# SH-SwitchNode-CT1_Shield.net
KiCad netlist of a schematic drawn in EAGLE
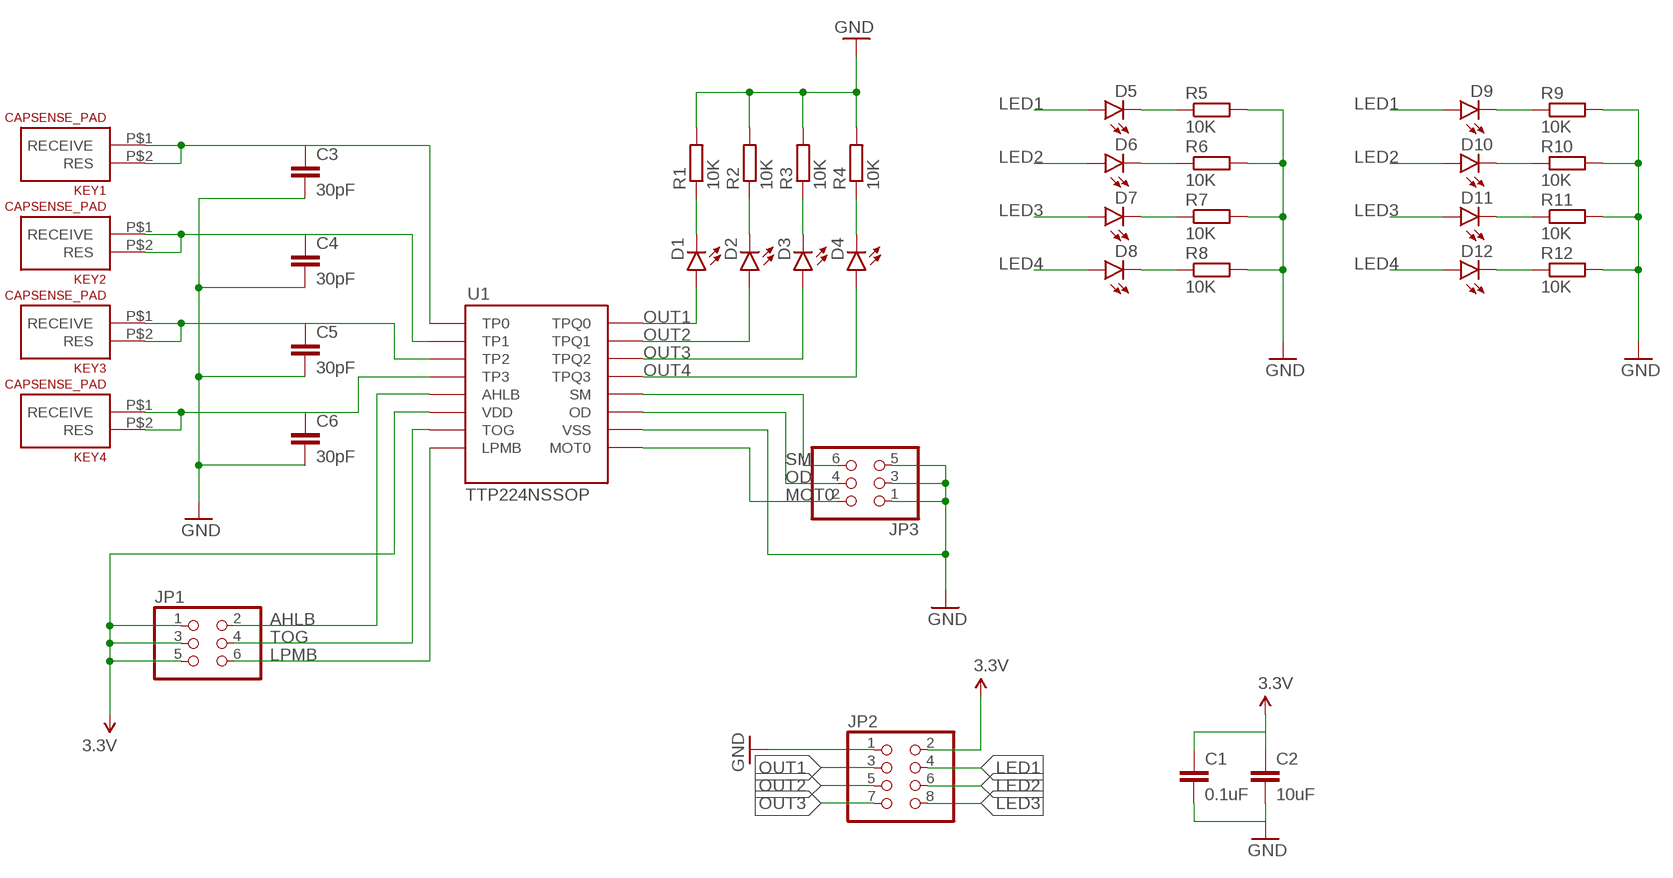
[diagram p0: schematic, sheet 1]

(export (version "E")
  (design (tool "Eeschema 10.0.6"))
  (components
    (comp (ref "C1")
      (value "0.1uF")
      (footprint "eagle-import:0805")
      (libsource (lib "eagle-import") (part "CAP0805"))
    )
    (comp (ref "C2")
      (value "10uF")
      (footprint "eagle-import:0805")
      (libsource (lib "eagle-import") (part "CAP0805"))
    )
    (comp (ref "C3")
      (value "30pF")
      (footprint "eagle-import:0805")
      (libsource (lib "eagle-import") (part "CAP0805"))
    )
    (comp (ref "C4")
      (value "30pF")
      (footprint "eagle-import:0805")
      (libsource (lib "eagle-import") (part "CAP0805"))
    )
    (comp (ref "C5")
      (value "30pF")
      (footprint "eagle-import:0805")
      (libsource (lib "eagle-import") (part "CAP0805"))
    )
    (comp (ref "C6")
      (value "30pF")
      (footprint "eagle-import:0805")
      (libsource (lib "eagle-import") (part "CAP0805"))
    )
    (comp (ref "D1")
      (value "LED1206-BOTTOM")
      (footprint "eagle-import:LED-1206-BOTTOM")
      (libsource (lib "eagle-import") (part "LED1206-BOTTOM"))
    )
    (comp (ref "D2")
      (value "LED1206-BOTTOM")
      (footprint "eagle-import:LED-1206-BOTTOM")
      (libsource (lib "eagle-import") (part "LED1206-BOTTOM"))
    )
    (comp (ref "D3")
      (value "LED1206-BOTTOM")
      (footprint "eagle-import:LED-1206-BOTTOM")
      (libsource (lib "eagle-import") (part "LED1206-BOTTOM"))
    )
    (comp (ref "D4")
      (value "LED1206-BOTTOM")
      (footprint "eagle-import:LED-1206-BOTTOM")
      (libsource (lib "eagle-import") (part "LED1206-BOTTOM"))
    )
    (comp (ref "D5")
      (value "LED1206-BOTTOM")
      (footprint "eagle-import:LED-1206-BOTTOM")
      (libsource (lib "eagle-import") (part "LED1206-BOTTOM"))
    )
    (comp (ref "D6")
      (value "LED1206-BOTTOM")
      (footprint "eagle-import:LED-1206-BOTTOM")
      (libsource (lib "eagle-import") (part "LED1206-BOTTOM"))
    )
    (comp (ref "D7")
      (value "LED1206-BOTTOM")
      (footprint "eagle-import:LED-1206-BOTTOM")
      (libsource (lib "eagle-import") (part "LED1206-BOTTOM"))
    )
    (comp (ref "D8")
      (value "LED1206-BOTTOM")
      (footprint "eagle-import:LED-1206-BOTTOM")
      (libsource (lib "eagle-import") (part "LED1206-BOTTOM"))
    )
    (comp (ref "D9")
      (value "LED1206-BOTTOM")
      (footprint "eagle-import:LED-1206-BOTTOM")
      (libsource (lib "eagle-import") (part "LED1206-BOTTOM"))
    )
    (comp (ref "D10")
      (value "LED1206-BOTTOM")
      (footprint "eagle-import:LED-1206-BOTTOM")
      (libsource (lib "eagle-import") (part "LED1206-BOTTOM"))
    )
    (comp (ref "D11")
      (value "LED1206-BOTTOM")
      (footprint "eagle-import:LED-1206-BOTTOM")
      (libsource (lib "eagle-import") (part "LED1206-BOTTOM"))
    )
    (comp (ref "D12")
      (value "LED1206-BOTTOM")
      (footprint "eagle-import:LED-1206-BOTTOM")
      (libsource (lib "eagle-import") (part "LED1206-BOTTOM"))
    )
    (comp (ref "JP1")
      (value "PINHD-2X3")
      (footprint "eagle-import:2X03")
      (libsource (lib "eagle-import") (part "PINHD-2X3"))
    )
    (comp (ref "JP2")
      (value "PINHD-2X4")
      (footprint "eagle-import:2X04")
      (libsource (lib "eagle-import") (part "PINHD-2X4"))
    )
    (comp (ref "JP3")
      (value "PINHD-2X3")
      (footprint "eagle-import:2X03")
      (libsource (lib "eagle-import") (part "PINHD-2X3"))
    )
    (comp (ref "KEY1")
      (value "CAPSENSE_PAD")
      (footprint "eagle-import:CAPSENSE_PAD")
      (libsource (lib "eagle-import") (part "CAPSENSE_PAD"))
    )
    (comp (ref "KEY2")
      (value "CAPSENSE_PAD")
      (footprint "eagle-import:CAPSENSE_PAD")
      (libsource (lib "eagle-import") (part "CAPSENSE_PAD"))
    )
    (comp (ref "KEY3")
      (value "CAPSENSE_PAD")
      (footprint "eagle-import:CAPSENSE_PAD")
      (libsource (lib "eagle-import") (part "CAPSENSE_PAD"))
    )
    (comp (ref "KEY4")
      (value "CAPSENSE_PAD")
      (footprint "eagle-import:CAPSENSE_PAD")
      (libsource (lib "eagle-import") (part "CAPSENSE_PAD"))
    )
    (comp (ref "R1")
      (value "10K")
      (footprint "eagle-import:R0805")
      (libsource (lib "eagle-import") (part "R-EU_R0805"))
    )
    (comp (ref "R2")
      (value "10K")
      (footprint "eagle-import:R0805")
      (libsource (lib "eagle-import") (part "R-EU_R0805"))
    )
    (comp (ref "R3")
      (value "10K")
      (footprint "eagle-import:R0805")
      (libsource (lib "eagle-import") (part "R-EU_R0805"))
    )
    (comp (ref "R4")
      (value "10K")
      (footprint "eagle-import:R0805")
      (libsource (lib "eagle-import") (part "R-EU_R0805"))
    )
    (comp (ref "R5")
      (value "10K")
      (footprint "eagle-import:R0805")
      (libsource (lib "eagle-import") (part "R-EU_R0805"))
    )
    (comp (ref "R6")
      (value "10K")
      (footprint "eagle-import:R0805")
      (libsource (lib "eagle-import") (part "R-EU_R0805"))
    )
    (comp (ref "R7")
      (value "10K")
      (footprint "eagle-import:R0805")
      (libsource (lib "eagle-import") (part "R-EU_R0805"))
    )
    (comp (ref "R8")
      (value "10K")
      (footprint "eagle-import:R0805")
      (libsource (lib "eagle-import") (part "R-EU_R0805"))
    )
    (comp (ref "R9")
      (value "10K")
      (footprint "eagle-import:R0805")
      (libsource (lib "eagle-import") (part "R-EU_R0805"))
    )
    (comp (ref "R10")
      (value "10K")
      (footprint "eagle-import:R0805")
      (libsource (lib "eagle-import") (part "R-EU_R0805"))
    )
    (comp (ref "R11")
      (value "10K")
      (footprint "eagle-import:R0805")
      (libsource (lib "eagle-import") (part "R-EU_R0805"))
    )
    (comp (ref "R12")
      (value "10K")
      (footprint "eagle-import:R0805")
      (libsource (lib "eagle-import") (part "R-EU_R0805"))
    )
    (comp (ref "U1")
      (value "TTP224NSSOP")
      (footprint "eagle-import:SSOP16")
      (libsource (lib "eagle-import") (part "TTP224NSSOP"))
    )
  )
  (nets
    (net (code "1") (name "/AHLB") (class "Default")
      (node (ref "JP1") (pin "2") (pinfunction "2_2") (pintype "passive"))
      (node (ref "U1") (pin "5") (pinfunction "AHLB_5") (pintype "bidirectional"))
    )
    (net (code "2") (name "/LED4") (class "Default")
      (node (ref "D12") (pin "A") (pinfunction "A_A") (pintype "passive"))
      (node (ref "D8") (pin "A") (pinfunction "A_A") (pintype "passive"))
    )
    (net (code "3") (name "/LPMB") (class "Default")
      (node (ref "JP1") (pin "6") (pinfunction "6_6") (pintype "passive"))
      (node (ref "U1") (pin "8") (pinfunction "LPMB_8") (pintype "bidirectional"))
    )
    (net (code "4") (name "/MOT0") (class "Default")
      (node (ref "JP3") (pin "2") (pinfunction "2_2") (pintype "passive"))
      (node (ref "U1") (pin "9") (pinfunction "MOT0_9") (pintype "bidirectional"))
    )
    (net (code "5") (name "/OD") (class "Default")
      (node (ref "JP3") (pin "4") (pinfunction "4_4") (pintype "passive"))
      (node (ref "U1") (pin "11") (pinfunction "OD_11") (pintype "bidirectional"))
    )
    (net (code "6") (name "/OUT4") (class "Default")
      (node (ref "D4") (pin "A") (pinfunction "A_A") (pintype "passive"))
      (node (ref "U1") (pin "13") (pinfunction "TPQ3_13") (pintype "output"))
    )
    (net (code "7") (name "/SM") (class "Default")
      (node (ref "JP3") (pin "6") (pinfunction "6_6") (pintype "passive"))
      (node (ref "U1") (pin "12") (pinfunction "SM_12") (pintype "bidirectional"))
    )
    (net (code "8") (name "/TOG") (class "Default")
      (node (ref "JP1") (pin "4") (pinfunction "4_4") (pintype "passive"))
      (node (ref "U1") (pin "7") (pinfunction "TOG_7") (pintype "bidirectional"))
    )
    (net (code "9") (name "3.3V") (class "Default")
      (node (ref "C1") (pin "1") (pinfunction "1_1") (pintype "passive"))
      (node (ref "C2") (pin "1") (pinfunction "1_1") (pintype "passive"))
      (node (ref "JP1") (pin "1") (pinfunction "1_1") (pintype "passive"))
      (node (ref "JP1") (pin "3") (pinfunction "3_3") (pintype "passive"))
      (node (ref "JP1") (pin "5") (pinfunction "5_5") (pintype "passive"))
      (node (ref "JP2") (pin "2") (pinfunction "2_2") (pintype "passive"))
      (node (ref "U1") (pin "6") (pinfunction "VDD_6") (pintype "power_in"))
    )
    (net (code "10") (name "GND") (class "Default")
      (node (ref "C1") (pin "2") (pinfunction "2_2") (pintype "passive"))
      (node (ref "C2") (pin "2") (pinfunction "2_2") (pintype "passive"))
      (node (ref "C3") (pin "2") (pinfunction "2_2") (pintype "passive"))
      (node (ref "C4") (pin "2") (pinfunction "2_2") (pintype "passive"))
      (node (ref "C5") (pin "2") (pinfunction "2_2") (pintype "passive"))
      (node (ref "C6") (pin "2") (pinfunction "2_2") (pintype "passive"))
      (node (ref "JP2") (pin "1") (pinfunction "1_1") (pintype "passive"))
      (node (ref "JP3") (pin "1") (pinfunction "1_1") (pintype "passive"))
      (node (ref "JP3") (pin "3") (pinfunction "3_3") (pintype "passive"))
      (node (ref "JP3") (pin "5") (pinfunction "5_5") (pintype "passive"))
      (node (ref "R1") (pin "2") (pinfunction "2_2") (pintype "passive"))
      (node (ref "R10") (pin "2") (pinfunction "2_2") (pintype "passive"))
      (node (ref "R11") (pin "2") (pinfunction "2_2") (pintype "passive"))
      (node (ref "R12") (pin "2") (pinfunction "2_2") (pintype "passive"))
      (node (ref "R2") (pin "2") (pinfunction "2_2") (pintype "passive"))
      (node (ref "R3") (pin "2") (pinfunction "2_2") (pintype "passive"))
      (node (ref "R4") (pin "2") (pinfunction "2_2") (pintype "passive"))
      (node (ref "R5") (pin "2") (pinfunction "2_2") (pintype "passive"))
      (node (ref "R6") (pin "2") (pinfunction "2_2") (pintype "passive"))
      (node (ref "R7") (pin "2") (pinfunction "2_2") (pintype "passive"))
      (node (ref "R8") (pin "2") (pinfunction "2_2") (pintype "passive"))
      (node (ref "R9") (pin "2") (pinfunction "2_2") (pintype "passive"))
      (node (ref "U1") (pin "10") (pinfunction "VSS_10") (pintype "power_in"))
    )
    (net (code "11") (name "LED1") (class "Default")
      (node (ref "D5") (pin "A") (pinfunction "A_A") (pintype "passive"))
      (node (ref "D9") (pin "A") (pinfunction "A_A") (pintype "passive"))
      (node (ref "JP2") (pin "4") (pinfunction "4_4") (pintype "passive"))
    )
    (net (code "12") (name "LED2") (class "Default")
      (node (ref "D10") (pin "A") (pinfunction "A_A") (pintype "passive"))
      (node (ref "D6") (pin "A") (pinfunction "A_A") (pintype "passive"))
      (node (ref "JP2") (pin "6") (pinfunction "6_6") (pintype "passive"))
    )
    (net (code "13") (name "LED3") (class "Default")
      (node (ref "D11") (pin "A") (pinfunction "A_A") (pintype "passive"))
      (node (ref "D7") (pin "A") (pinfunction "A_A") (pintype "passive"))
      (node (ref "JP2") (pin "8") (pinfunction "8_8") (pintype "passive"))
    )
    (net (code "14") (name "Net-(D1-PadC)") (class "Default")
      (node (ref "D1") (pin "C") (pinfunction "C_C") (pintype "passive"))
      (node (ref "R1") (pin "1") (pinfunction "1_1") (pintype "passive"))
    )
    (net (code "15") (name "Net-(D2-PadC)") (class "Default")
      (node (ref "D2") (pin "C") (pinfunction "C_C") (pintype "passive"))
      (node (ref "R2") (pin "1") (pinfunction "1_1") (pintype "passive"))
    )
    (net (code "16") (name "Net-(D3-PadC)") (class "Default")
      (node (ref "D3") (pin "C") (pinfunction "C_C") (pintype "passive"))
      (node (ref "R3") (pin "1") (pinfunction "1_1") (pintype "passive"))
    )
    (net (code "17") (name "Net-(D4-PadC)") (class "Default")
      (node (ref "D4") (pin "C") (pinfunction "C_C") (pintype "passive"))
      (node (ref "R4") (pin "1") (pinfunction "1_1") (pintype "passive"))
    )
    (net (code "18") (name "Net-(D5-PadC)") (class "Default")
      (node (ref "D5") (pin "C") (pinfunction "C_C") (pintype "passive"))
      (node (ref "R5") (pin "1") (pinfunction "1_1") (pintype "passive"))
    )
    (net (code "19") (name "Net-(D6-PadC)") (class "Default")
      (node (ref "D6") (pin "C") (pinfunction "C_C") (pintype "passive"))
      (node (ref "R6") (pin "1") (pinfunction "1_1") (pintype "passive"))
    )
    (net (code "20") (name "Net-(D7-PadC)") (class "Default")
      (node (ref "D7") (pin "C") (pinfunction "C_C") (pintype "passive"))
      (node (ref "R7") (pin "1") (pinfunction "1_1") (pintype "passive"))
    )
    (net (code "21") (name "Net-(D8-PadC)") (class "Default")
      (node (ref "D8") (pin "C") (pinfunction "C_C") (pintype "passive"))
      (node (ref "R8") (pin "1") (pinfunction "1_1") (pintype "passive"))
    )
    (net (code "22") (name "Net-(D9-PadC)") (class "Default")
      (node (ref "D9") (pin "C") (pinfunction "C_C") (pintype "passive"))
      (node (ref "R9") (pin "1") (pinfunction "1_1") (pintype "passive"))
    )
    (net (code "23") (name "Net-(D10-PadC)") (class "Default")
      (node (ref "D10") (pin "C") (pinfunction "C_C") (pintype "passive"))
      (node (ref "R10") (pin "1") (pinfunction "1_1") (pintype "passive"))
    )
    (net (code "24") (name "Net-(D11-PadC)") (class "Default")
      (node (ref "D11") (pin "C") (pinfunction "C_C") (pintype "passive"))
      (node (ref "R11") (pin "1") (pinfunction "1_1") (pintype "passive"))
    )
    (net (code "25") (name "Net-(D12-PadC)") (class "Default")
      (node (ref "D12") (pin "C") (pinfunction "C_C") (pintype "passive"))
      (node (ref "R12") (pin "1") (pinfunction "1_1") (pintype "passive"))
    )
    (net (code "26") (name "Net-(KEY1-RECEIVE)") (class "Default")
      (node (ref "C3") (pin "1") (pinfunction "1_1") (pintype "passive"))
      (node (ref "KEY1") (pin "P$1") (pinfunction "RECEIVE_P$1") (pintype "bidirectional"))
      (node (ref "KEY1") (pin "P$2") (pinfunction "RES_P$2") (pintype "bidirectional"))
      (node (ref "U1") (pin "1") (pinfunction "TP0_1") (pintype "bidirectional"))
    )
    (net (code "27") (name "Net-(KEY2-RECEIVE)") (class "Default")
      (node (ref "C4") (pin "1") (pinfunction "1_1") (pintype "passive"))
      (node (ref "KEY2") (pin "P$1") (pinfunction "RECEIVE_P$1") (pintype "bidirectional"))
      (node (ref "KEY2") (pin "P$2") (pinfunction "RES_P$2") (pintype "bidirectional"))
      (node (ref "U1") (pin "2") (pinfunction "TP1_2") (pintype "bidirectional"))
    )
    (net (code "28") (name "Net-(KEY3-RECEIVE)") (class "Default")
      (node (ref "C5") (pin "1") (pinfunction "1_1") (pintype "passive"))
      (node (ref "KEY3") (pin "P$1") (pinfunction "RECEIVE_P$1") (pintype "bidirectional"))
      (node (ref "KEY3") (pin "P$2") (pinfunction "RES_P$2") (pintype "bidirectional"))
      (node (ref "U1") (pin "3") (pinfunction "TP2_3") (pintype "bidirectional"))
    )
    (net (code "29") (name "Net-(KEY4-RECEIVE)") (class "Default")
      (node (ref "C6") (pin "1") (pinfunction "1_1") (pintype "passive"))
      (node (ref "KEY4") (pin "P$1") (pinfunction "RECEIVE_P$1") (pintype "bidirectional"))
      (node (ref "KEY4") (pin "P$2") (pinfunction "RES_P$2") (pintype "bidirectional"))
      (node (ref "U1") (pin "4") (pinfunction "TP3_4") (pintype "bidirectional"))
    )
    (net (code "30") (name "OUT1") (class "Default")
      (node (ref "D1") (pin "A") (pinfunction "A_A") (pintype "passive"))
      (node (ref "JP2") (pin "3") (pinfunction "3_3") (pintype "passive"))
      (node (ref "U1") (pin "16") (pinfunction "TPQ0_16") (pintype "output"))
    )
    (net (code "31") (name "OUT2") (class "Default")
      (node (ref "D2") (pin "A") (pinfunction "A_A") (pintype "passive"))
      (node (ref "JP2") (pin "5") (pinfunction "5_5") (pintype "passive"))
      (node (ref "U1") (pin "15") (pinfunction "TPQ1_15") (pintype "output"))
    )
    (net (code "32") (name "OUT3") (class "Default")
      (node (ref "D3") (pin "A") (pinfunction "A_A") (pintype "passive"))
      (node (ref "JP2") (pin "7") (pinfunction "7_7") (pintype "passive"))
      (node (ref "U1") (pin "14") (pinfunction "TPQ2_14") (pintype "output"))
    )
  )
)
